# 08_iMX_8X_MEMORY.net
KiCad netlist of a schematic drawn in Altium Designer
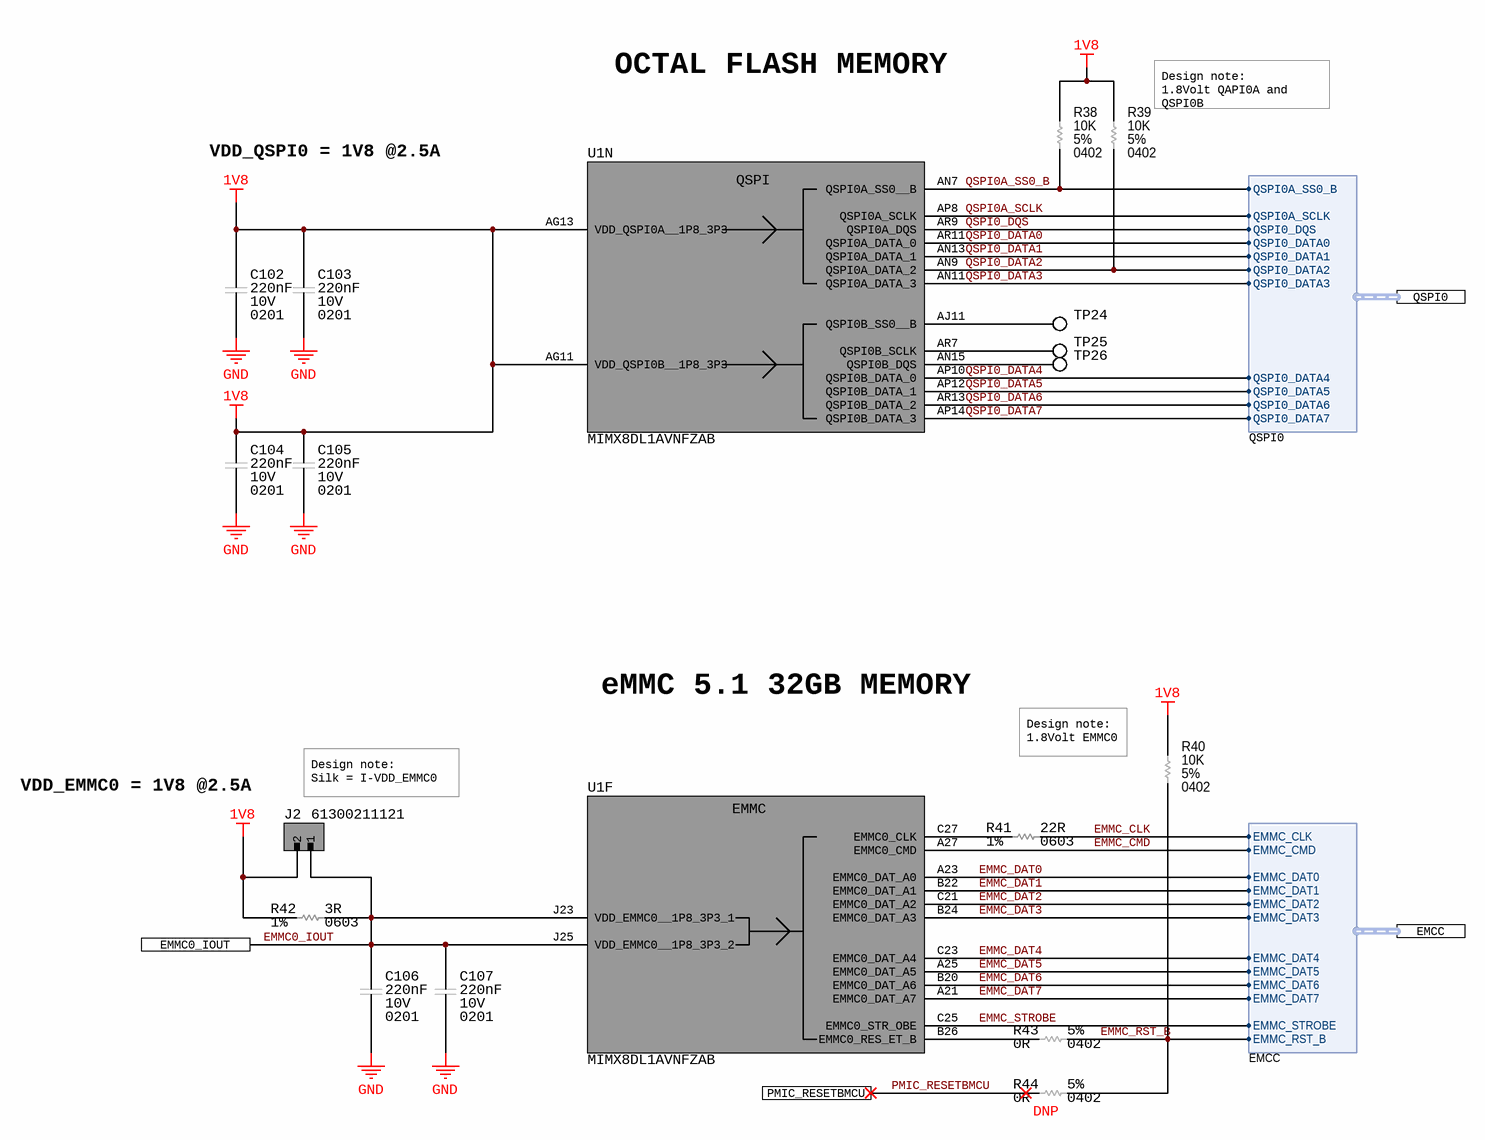
[diagram p0: 08_iMX 8X_MEMORY.SchDoc]

(export (version "E")
  (design (tool "Eeschema 10.0.6"))
  (components
    (comp (ref "C102")
      (value "LMK063BJ224MP-F")
      (footprint "CAP_0201_CAPC0603X03N")
      (description "Multilayer Ceramic Capacitors (High dielectric type), 10V, 0.22 uF, ± 20 %, 0201, X5R, RoHS")
      (fields
        (field (name "MANUFACTURER") "Taiyo Yuden")
        (field (name "TOLERANCE") "20%")
        (field (name "VOLTAGE RATING (DC)") "10V")
        (field (name "CAPACITANCE") "220nF")
        (field (name "CASE/PACKAGE") "0201")
      )
      (libsource (lib "Electronic Devices_LIB") (part "CAP_0.22UF_10V_X5R_0201"))
    )
    (comp (ref "C103")
      (value "LMK063BJ224MP-F")
      (footprint "CAP_0201_CAPC0603X03N")
      (description "Multilayer Ceramic Capacitors (High dielectric type), 10V, 0.22 uF, ± 20 %, 0201, X5R, RoHS")
      (fields
        (field (name "MANUFACTURER") "Taiyo Yuden")
        (field (name "TOLERANCE") "20%")
        (field (name "VOLTAGE RATING (DC)") "10V")
        (field (name "CAPACITANCE") "220nF")
        (field (name "CASE/PACKAGE") "0201")
      )
      (libsource (lib "Electronic Devices_LIB") (part "CAP_0.22UF_10V_X5R_0201"))
    )
    (comp (ref "C104")
      (value "LMK063BJ224MP-F")
      (footprint "CAP_0201_CAPC0603X03N")
      (description "Multilayer Ceramic Capacitors (High dielectric type), 10V, 0.22 uF, ± 20 %, 0201, X5R, RoHS")
      (fields
        (field (name "MANUFACTURER") "Taiyo Yuden")
        (field (name "TOLERANCE") "20%")
        (field (name "VOLTAGE RATING (DC)") "10V")
        (field (name "CAPACITANCE") "220nF")
        (field (name "CASE/PACKAGE") "0201")
      )
      (libsource (lib "Electronic Devices_LIB") (part "CAP_0.22UF_10V_X5R_0201"))
    )
    (comp (ref "C105")
      (value "LMK063BJ224MP-F")
      (footprint "CAP_0201_CAPC0603X03N")
      (description "Multilayer Ceramic Capacitors (High dielectric type), 10V, 0.22 uF, ± 20 %, 0201, X5R, RoHS")
      (fields
        (field (name "MANUFACTURER") "Taiyo Yuden")
        (field (name "TOLERANCE") "20%")
        (field (name "VOLTAGE RATING (DC)") "10V")
        (field (name "CAPACITANCE") "220nF")
        (field (name "CASE/PACKAGE") "0201")
      )
      (libsource (lib "Electronic Devices_LIB") (part "CAP_0.22UF_10V_X5R_0201"))
    )
    (comp (ref "C106")
      (value "LMK063BJ224MP-F")
      (footprint "CAP_0201_CAPC0603X03N")
      (description "Multilayer Ceramic Capacitors (High dielectric type), 10V, 0.22 uF, ± 20 %, 0201, X5R, RoHS")
      (fields
        (field (name "MANUFACTURER") "Taiyo Yuden")
        (field (name "TOLERANCE") "20%")
        (field (name "VOLTAGE RATING (DC)") "10V")
        (field (name "CAPACITANCE") "220nF")
        (field (name "CASE/PACKAGE") "0201")
      )
      (libsource (lib "Electronic Devices_LIB") (part "CAP_0.22UF_10V_X5R_0201"))
    )
    (comp (ref "C107")
      (value "LMK063BJ224MP-F")
      (footprint "CAP_0201_CAPC0603X03N")
      (description "Multilayer Ceramic Capacitors (High dielectric type), 10V, 0.22 uF, ± 20 %, 0201, X5R, RoHS")
      (fields
        (field (name "MANUFACTURER") "Taiyo Yuden")
        (field (name "TOLERANCE") "20%")
        (field (name "VOLTAGE RATING (DC)") "10V")
        (field (name "CAPACITANCE") "220nF")
        (field (name "CASE/PACKAGE") "0201")
      )
      (libsource (lib "Electronic Devices_LIB") (part "CAP_0.22UF_10V_X5R_0201"))
    )
    (comp (ref "J2")
      (value "61300211121")
      (footprint "HEADER_MALE_HDRV2W110P0X254_1X2_508X254X854P")
      (description "THT Vertical Pin Header WR-PHD, Pitch 2.54 mm, Single Row, 2 pins")
      (fields (field (name "MANUFACTURER") "Wurth Electronics"))
      (libsource (lib "Electronic Devices_LIB") (part "CONN_HEADER_MALE_2P_2.54_61300211121"))
    )
    (comp (ref "R38")
      (value "ERJ-2GEJ103X")
      (footprint "RES_0402_RESC1005X04N")
      (description "Res Thick Film 0402 10K Ohm 5% 1/10W ±200ppm/°C Molded SMD Punched Carrier T/R")
      (fields
        (field (name "MANUFACTURER") "Panasonic")
        (field (name "TOLERANCE") "5%")
        (field (name "RESISTANCE") "10K")
        (field (name "CASE/PACKAGE") "0402")
      )
      (libsource (lib "Electronic Devices_LIB") (part "RES_10K_5%_100mW_0402"))
    )
    (comp (ref "R39")
      (value "ERJ-2GEJ103X")
      (footprint "RES_0402_RESC1005X04N")
      (description "Res Thick Film 0402 10K Ohm 5% 1/10W ±200ppm/°C Molded SMD Punched Carrier T/R")
      (fields
        (field (name "MANUFACTURER") "Panasonic")
        (field (name "TOLERANCE") "5%")
        (field (name "RESISTANCE") "10K")
        (field (name "CASE/PACKAGE") "0402")
      )
      (libsource (lib "Electronic Devices_LIB") (part "RES_10K_5%_100mW_0402"))
    )
    (comp (ref "R40")
      (value "ERJ-2GEJ103X")
      (footprint "RES_0402_RESC1005X04N")
      (description "Res Thick Film 0402 10K Ohm 5% 1/10W ±200ppm/°C Molded SMD Punched Carrier T/R")
      (fields
        (field (name "MANUFACTURER") "Panasonic")
        (field (name "TOLERANCE") "5%")
        (field (name "RESISTANCE") "10K")
        (field (name "CASE/PACKAGE") "0402")
      )
      (libsource (lib "Electronic Devices_LIB") (part "RES_10K_5%_100mW_0402"))
    )
    (comp (ref "R41")
      (value "RC0603FR-0722RL")
      (footprint "RES_0603_RESC1608X04N")
      (description "Res Thick Film 0603 22 Ohm 1% 0.1W(1/10W) ±100ppm/C Pad SMD T/R")
      (fields
        (field (name "MANUFACTURER") "Yageo")
        (field (name "TOLERANCE") "1%")
        (field (name "RESISTANCE") "22R")
        (field (name "CASE/PACKAGE") "0603")
      )
      (libsource (lib "Electronic Devices_LIB") (part "RES_22R_1%_100mW_0603"))
    )
    (comp (ref "R42")
      (value "RMCF0603FT3R00")
      (footprint "RES_0603_RESC1608X04N")
      (description "Res Thick Film 0603 3 Ohm 1% 0.1W(1/10W) ±200ppm/C Pad SMD Automotive T/R")
      (fields
        (field (name "MANUFACTURER") "Stackpole Electronics")
        (field (name "TOLERANCE") "1%")
        (field (name "RESISTANCE") "3R")
        (field (name "CASE/PACKAGE") "0603")
      )
      (libsource (lib "Electronic Devices_LIB") (part "RES_3R_100mW_0603"))
    )
    (comp (ref "R43")
      (value "ERJ-2GE0R00X")
      (footprint "RES_0402_RESC1005X04N")
      (description "SMD Chip Resistor, Jumper, 0 ohm, 100 mW, 0402 [1005 Metric], Thick Film, General Purpose")
      (fields
        (field (name "MANUFACTURER") "Panasonic")
        (field (name "CASE CODE (IMPERIAL)") "0402")
        (field (name "TOLERANCE") "5%")
        (field (name "RESISTANCE") "0R")
      )
      (libsource (lib "Electronic Devices_LIB") (part "RES_0R_5%_100mW_0402"))
    )
    (comp (ref "R44")
      (value "ERJ-2GE0R00X")
      (footprint "RES_0402_RESC1005X04N")
      (description "SMD Chip Resistor, Jumper, 0 ohm, 100 mW, 0402 [1005 Metric], Thick Film, General Purpose")
      (fields
        (field (name "MANUFACTURER") "Panasonic")
        (field (name "CASE CODE (IMPERIAL)") "0402")
        (field (name "TOLERANCE") "5%")
        (field (name "RESISTANCE") "0R")
      )
      (libsource (lib "Electronic Devices_LIB") (part "RES_0R_5%_100mW_0402"))
    )
    (comp (ref "TP24")
      (value "NO COMPONENT")
      (footprint "TP_PAD_0.5MM_SMD_ROUND")
      (description "Test Point, SMD pad, round, 1.5mm, 1.6mm, 3mm diameter")
      (libsource (lib "Electronic Devices_LIB") (part "TP_PAD_SMD_SMALL"))
    )
    (comp (ref "TP25")
      (value "NO COMPONENT")
      (footprint "TP_PAD_0.5MM_SMD_ROUND")
      (description "Test Point, SMD pad, round, 1.5mm, 1.6mm, 3mm diameter")
      (libsource (lib "Electronic Devices_LIB") (part "TP_PAD_SMD_SMALL"))
    )
    (comp (ref "TP26")
      (value "NO COMPONENT")
      (footprint "TP_PAD_0.5MM_SMD_ROUND")
      (description "Test Point, SMD pad, round, 1.5mm, 1.6mm, 3mm diameter")
      (libsource (lib "Electronic Devices_LIB") (part "TP_PAD_SMD_SMALL"))
    )
    (comp (ref "U1")
      (value "MIMX8DL1AVNFZAB")
      (footprint "MIMX8DL1AVNFZAB")
      (description "I.MX8 Dxl 15SQ / Tray Rohs Compliant: Yes")
      (fields (field (name "MANUFACTURER") "NXP Semiconductors"))
      (libsource (lib "Electronic Devices_LIB") (part "IC_MPU_ARM_1.2GHz_MIMX8DL1AVNFZAB"))
    )
  )
  (nets
    (net (code "3") (name "/EMMC0_IOUT") (class "Default")
      (node (ref "C106") (pin "2") (pinfunction "2_2") (pintype "passive"))
      (node (ref "C107") (pin "2") (pinfunction "2_2") (pintype "passive"))
      (node (ref "J2") (pin "1") (pinfunction "1_1") (pintype "passive"))
      (node (ref "R42") (pin "2") (pinfunction "2_2") (pintype "passive"))
      (node (ref "U1") (pin "J23") (pinfunction "VDD_EMMC0__1P8_3P3_1_J23") (pintype "passive"))
      (node (ref "U1") (pin "J25") (pinfunction "VDD_EMMC0__1P8_3P3_2_J25") (pintype "passive"))
    )
    (net (code "4") (name "/EMMC_CLK") (class "Default")
      (node (ref "R41") (pin "2") (pinfunction "2_2") (pintype "passive"))
    )
    (net (code "5") (name "/EMMC_CMD") (class "Default")
      (node (ref "U1") (pin "A27") (pinfunction "EMMC0_CMD_A27") (pintype "passive"))
    )
    (net (code "6") (name "/EMMC_DAT0") (class "Default")
      (node (ref "U1") (pin "A23") (pinfunction "EMMC0_DAT_A0_A23") (pintype "passive"))
    )
    (net (code "7") (name "/EMMC_DAT1") (class "Default")
      (node (ref "U1") (pin "B22") (pinfunction "EMMC0_DAT_A1_B22") (pintype "passive"))
    )
    (net (code "8") (name "/EMMC_DAT2") (class "Default")
      (node (ref "U1") (pin "C21") (pinfunction "EMMC0_DAT_A2_C21") (pintype "passive"))
    )
    (net (code "9") (name "/EMMC_DAT3") (class "Default")
      (node (ref "U1") (pin "B24") (pinfunction "EMMC0_DAT_A3_B24") (pintype "passive"))
    )
    (net (code "10") (name "/EMMC_DAT4") (class "Default")
      (node (ref "U1") (pin "C23") (pinfunction "EMMC0_DAT_A4_C23") (pintype "passive"))
    )
    (net (code "11") (name "/EMMC_DAT5") (class "Default")
      (node (ref "U1") (pin "A25") (pinfunction "EMMC0_DAT_A5_A25") (pintype "passive"))
    )
    (net (code "12") (name "/EMMC_DAT6") (class "Default")
      (node (ref "U1") (pin "B20") (pinfunction "EMMC0_DAT_A6_B20") (pintype "passive"))
    )
    (net (code "13") (name "/EMMC_DAT7") (class "Default")
      (node (ref "U1") (pin "A21") (pinfunction "EMMC0_DAT_A7_A21") (pintype "passive"))
    )
    (net (code "14") (name "/EMMC_RST_B") (class "Default")
      (node (ref "R40") (pin "1") (pinfunction "1_1") (pintype "passive"))
      (node (ref "R43") (pin "2") (pinfunction "2_2") (pintype "passive"))
      (node (ref "R44") (pin "2") (pinfunction "2_2") (pintype "passive"))
    )
    (net (code "15") (name "/EMMC_STROBE") (class "Default")
      (node (ref "U1") (pin "C25") (pinfunction "EMMC0_STR_OBE_C25") (pintype "passive"))
    )
    (net (code "16") (name "/PMIC_RESETBMCU") (class "Default")
      (node (ref "R44") (pin "1") (pinfunction "1_1") (pintype "passive+no_connect"))
    )
    (net (code "17") (name "/QSPI0A_SCLK") (class "Default")
      (node (ref "U1") (pin "AP8") (pinfunction "QSPI0A_SCLK_AP8") (pintype "passive"))
    )
    (net (code "18") (name "/QSPI0A_SS0_B") (class "Default")
      (node (ref "R38") (pin "1") (pinfunction "1_1") (pintype "passive"))
      (node (ref "U1") (pin "AN7") (pinfunction "QSPI0A_SS0__B_AN7") (pintype "passive"))
    )
    (net (code "19") (name "/QSPI0_DATA0") (class "Default")
      (node (ref "U1") (pin "AR11") (pinfunction "QSPI0A_DATA_0_AR11") (pintype "passive"))
    )
    (net (code "20") (name "/QSPI0_DATA1") (class "Default")
      (node (ref "U1") (pin "AN13") (pinfunction "QSPI0A_DATA_1_AN13") (pintype "passive"))
    )
    (net (code "21") (name "/QSPI0_DATA2") (class "Default")
      (node (ref "R39") (pin "1") (pinfunction "1_1") (pintype "passive"))
      (node (ref "U1") (pin "AN9") (pinfunction "QSPI0A_DATA_2_AN9") (pintype "passive"))
    )
    (net (code "22") (name "/QSPI0_DATA3") (class "Default")
      (node (ref "U1") (pin "AN11") (pinfunction "QSPI0A_DATA_3_AN11") (pintype "passive"))
    )
    (net (code "23") (name "/QSPI0_DATA4") (class "Default")
      (node (ref "U1") (pin "AP10") (pinfunction "QSPI0B_DATA_0_AP10") (pintype "passive"))
    )
    (net (code "24") (name "/QSPI0_DATA5") (class "Default")
      (node (ref "U1") (pin "AP12") (pinfunction "QSPI0B_DATA_1_AP12") (pintype "passive"))
    )
    (net (code "25") (name "/QSPI0_DATA6") (class "Default")
      (node (ref "U1") (pin "AR13") (pinfunction "QSPI0B_DATA_2_AR13") (pintype "passive"))
    )
    (net (code "26") (name "/QSPI0_DATA7") (class "Default")
      (node (ref "U1") (pin "AP14") (pinfunction "QSPI0B_DATA_3_AP14") (pintype "passive"))
    )
    (net (code "27") (name "/QSPI0_DQS") (class "Default")
      (node (ref "U1") (pin "AR9") (pinfunction "QSPI0A_DQS_AR9") (pintype "passive"))
    )
    (net (code "30") (name "1V8") (class "Default")
      (node (ref "C102") (pin "2") (pinfunction "2_2") (pintype "passive"))
      (node (ref "C103") (pin "2") (pinfunction "2_2") (pintype "passive"))
      (node (ref "C104") (pin "2") (pinfunction "2_2") (pintype "passive"))
      (node (ref "C105") (pin "2") (pinfunction "2_2") (pintype "passive"))
      (node (ref "J2") (pin "2") (pinfunction "2_2") (pintype "passive"))
      (node (ref "R38") (pin "2") (pinfunction "2_2") (pintype "passive"))
      (node (ref "R39") (pin "2") (pinfunction "2_2") (pintype "passive"))
      (node (ref "R40") (pin "2") (pinfunction "2_2") (pintype "passive"))
      (node (ref "R42") (pin "1") (pinfunction "1_1") (pintype "passive"))
      (node (ref "U1") (pin "AG11") (pinfunction "VDD_QSPI0B__1P8_3P3_AG11") (pintype "passive"))
      (node (ref "U1") (pin "AG13") (pinfunction "VDD_QSPI0A__1P8_3P3_AG13") (pintype "passive"))
    )
    (net (code "31") (name "GND") (class "Default")
      (node (ref "C102") (pin "1") (pinfunction "1_1") (pintype "passive"))
      (node (ref "C103") (pin "1") (pinfunction "1_1") (pintype "passive"))
      (node (ref "C104") (pin "1") (pinfunction "1_1") (pintype "passive"))
      (node (ref "C105") (pin "1") (pinfunction "1_1") (pintype "passive"))
      (node (ref "C106") (pin "1") (pinfunction "1_1") (pintype "passive"))
      (node (ref "C107") (pin "1") (pinfunction "1_1") (pintype "passive"))
    )
    (net (code "32") (name "Net-(U1F-EMMC0_CLK)") (class "Default")
      (node (ref "R41") (pin "1") (pinfunction "1_1") (pintype "passive"))
      (node (ref "U1") (pin "C27") (pinfunction "EMMC0_CLK_C27") (pintype "passive"))
    )
    (net (code "33") (name "Net-(U1F-EMMC0_RES_ET_B)") (class "Default")
      (node (ref "R43") (pin "1") (pinfunction "1_1") (pintype "passive"))
      (node (ref "U1") (pin "B26") (pinfunction "EMMC0_RES_ET_B_B26") (pintype "passive"))
    )
    (net (code "34") (name "Net-(U1N-QSPI0B_DQS)") (class "Default")
      (node (ref "TP26") (pin "1") (pinfunction "1_1") (pintype "passive"))
      (node (ref "U1") (pin "AN15") (pinfunction "QSPI0B_DQS_AN15") (pintype "passive"))
    )
    (net (code "35") (name "Net-(U1N-QSPI0B_SCLK)") (class "Default")
      (node (ref "TP25") (pin "1") (pinfunction "1_1") (pintype "passive"))
      (node (ref "U1") (pin "AR7") (pinfunction "QSPI0B_SCLK_AR7") (pintype "passive"))
    )
    (net (code "36") (name "Net-(U1N-QSPI0B_SS0__B)") (class "Default")
      (node (ref "TP24") (pin "1") (pinfunction "1_1") (pintype "passive"))
      (node (ref "U1") (pin "AJ11") (pinfunction "QSPI0B_SS0__B_AJ11") (pintype "passive"))
    )
  )
)
